# RTC.net
KiCad netlist of a schematic drawn in Altium Designer
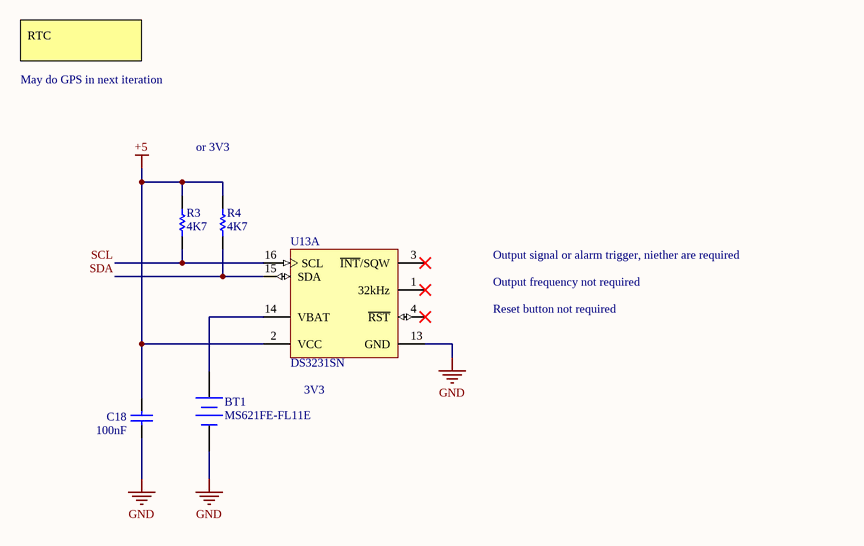
[diagram p0: RTC.SchDoc]

(export (version "E")
  (design (tool "Eeschema 10.0.6"))
  (components
    (comp (ref "BT1")
      (value "MS621FE-FL11E")
      (footprint "SEIK-MS621FE-FL11E-2_V")
      (description "MS Lihium Rechargeable Battery, 3 V, -20 to 60 degC, Tray")
      (fields (field (name "MANUFACTURER") "SeikoInstruments"))
      (libsource (lib "Altium Content Vault") (part "BATTERY_SINGLE-2"))
    )
    (comp (ref "C18")
      (value "100nF")
      (footprint "CAPC0603(1608)100_M")
      (description "CAP 100nF 16V ±5% 0603 (1608 Metric) Thickness 1mm SMD")
      (fields (field (name "TOLERANCE") "Â±5%"))
      (libsource (lib "Altium Content Vault") (part "CAP"))
    )
    (comp (ref "R3")
      (value "4K7")
      (footprint "RESC0603(1608)_N")
      (description "4K7 0.1W 5% 0603 (1608 Metric)  SMD")
      (fields (field (name "TOLERANCE") "5 %") (field (name "POWER") "0.1 W"))
      (libsource (lib "Altium Content Vault") (part "RES"))
    )
    (comp (ref "R4")
      (value "4K7")
      (footprint "RESC0603(1608)_N")
      (description "4K7 0.1W 5% 0603 (1608 Metric)  SMD")
      (fields (field (name "TOLERANCE") "5 %") (field (name "POWER") "0.1 W"))
      (libsource (lib "Altium Content Vault") (part "RES"))
    )
    (comp (ref "U13")
      (value "DS3231SN")
      (footprint "W16-H2_L")
      (description "Extremely Accurate I2C-Integrated Real-Time Clock/TCXO/Crystal, 16-Pin SO, -40 to 85 degC")
      (libsource (lib "Altium Content Vault") (part "MAX-RTC-16-DS3231S-W16#H2"))
    )
  )
  (nets
    (net (code "1") (name "+5") (class "Default")
      (node (ref "C18") (pin "2") (pinfunction "2_2") (pintype "passive"))
      (node (ref "R3") (pin "1") (pinfunction "1_1") (pintype "passive"))
      (node (ref "R4") (pin "2") (pinfunction "2_2") (pintype "passive"))
      (node (ref "U13") (pin "2") (pinfunction "VCC_2") (pintype "power_in"))
    )
    (net (code "2") (name "/SCL") (class "Default")
      (node (ref "R3") (pin "2") (pinfunction "2_2") (pintype "passive"))
      (node (ref "U13") (pin "16") (pinfunction "SCL_16") (pintype "input"))
    )
    (net (code "3") (name "/SDA") (class "Default")
      (node (ref "R4") (pin "1") (pinfunction "1_1") (pintype "passive"))
      (node (ref "U13") (pin "15") (pinfunction "SDA_15") (pintype "bidirectional"))
    )
    (net (code "4") (name "GND") (class "Default")
      (node (ref "BT1") (pin "2") (pinfunction "-_2") (pintype "passive"))
      (node (ref "C18") (pin "1") (pinfunction "1_1") (pintype "passive"))
      (node (ref "U13") (pin "13") (pinfunction "GND_13") (pintype "power_in"))
    )
    (net (code "5") (name "Net-(BT1-+)") (class "Default")
      (node (ref "BT1") (pin "1") (pinfunction "+_1") (pintype "passive"))
      (node (ref "U13") (pin "14") (pinfunction "VBAT_14") (pintype "power_in"))
    )
    (net (code "6") (name "unconnected-(U13A-32kHz-Pad1)") (class "Default")
      (node (ref "U13") (pin "1") (pinfunction "32kHz_1") (pintype "open_collector+no_connect"))
    )
    (net (code "7") (name "unconnected-(U13A-~{INT}{slash}SQW-Pad3)") (class "Default")
      (node (ref "U13") (pin "3") (pinfunction "~{INT}/SQW_3") (pintype "open_collector+no_connect"))
    )
    (net (code "8") (name "unconnected-(U13A-~{RST}-Pad4)") (class "Default")
      (node (ref "U13") (pin "4") (pinfunction "~{RST}_4") (pintype "bidirectional+no_connect"))
    )
  )
)
